# Bluetooth_Receiver.net
KiCad netlist of a schematic drawn in Altium Designer
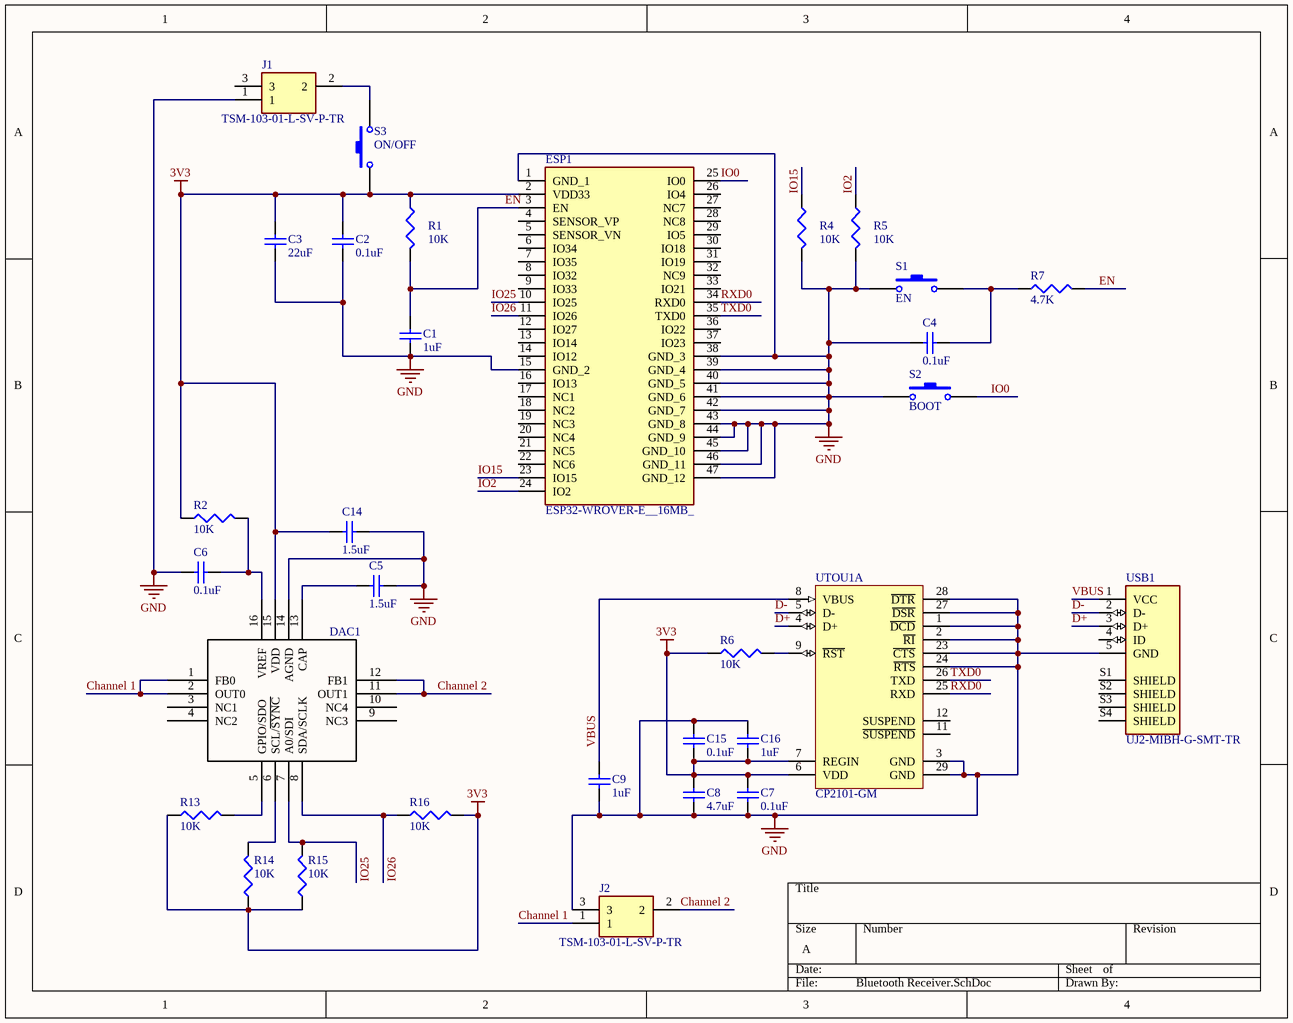
[diagram p0: Bluetooth Receiver.SchDoc]

(export (version "E")
  (design (tool "Eeschema 10.0.6"))
  (components
    (comp (ref "C1")
      (value "1uF")
      (footprint "1608[0603]")
      (description "Capacitor (Semiconductor SIM Model)")
      (fields (field (name "Comment") "Cap") (field (name "PUBLISHER") "Altium Limited"))
      (libsource (lib "Miscellaneous Devices") (part "Cap Semi"))
    )
    (comp (ref "C2")
      (value "0.1uF")
      (footprint "1608[0603]")
      (description "Capacitor (Semiconductor SIM Model)")
      (fields (field (name "Comment") "Cap") (field (name "PUBLISHER") "Altium Limited"))
      (libsource (lib "Miscellaneous Devices") (part "Cap Semi"))
    )
    (comp (ref "C3")
      (value "22uF")
      (footprint "1608[0603]")
      (description "Capacitor (Semiconductor SIM Model)")
      (fields (field (name "Comment") "Cap") (field (name "PUBLISHER") "Altium Limited"))
      (libsource (lib "Miscellaneous Devices") (part "Cap Semi"))
    )
    (comp (ref "C4")
      (value "0.1uF")
      (footprint "1608[0603]")
      (description "Capacitor (Semiconductor SIM Model)")
      (fields (field (name "Comment") "Cap") (field (name "PUBLISHER") "Altium Limited"))
      (libsource (lib "Miscellaneous Devices") (part "Cap Semi"))
    )
    (comp (ref "C5")
      (value "1.5uF")
      (footprint "1608[0603]")
      (description "Capacitor (Semiconductor SIM Model)")
      (fields (field (name "Comment") "Cap") (field (name "PUBLISHER") "Altium Limited"))
      (libsource (lib "Miscellaneous Devices") (part "Cap Semi"))
    )
    (comp (ref "C6")
      (value "0.1uF")
      (footprint "1608[0603]")
      (description "Capacitor (Semiconductor SIM Model)")
      (fields (field (name "Comment") "Cap") (field (name "PUBLISHER") "Altium Limited"))
      (libsource (lib "Miscellaneous Devices") (part "Cap Semi"))
    )
    (comp (ref "C7")
      (value "0.1uF")
      (footprint "1608[0603]")
      (description "Capacitor (Semiconductor SIM Model)")
      (fields (field (name "Comment") "Cap") (field (name "PUBLISHER") "Altium Limited"))
      (libsource (lib "Miscellaneous Devices") (part "Cap Semi"))
    )
    (comp (ref "C8")
      (value "4.7uF")
      (footprint "1608[0603]")
      (description "Capacitor (Semiconductor SIM Model)")
      (fields (field (name "Comment") "Cap") (field (name "PUBLISHER") "Altium Limited"))
      (libsource (lib "Miscellaneous Devices") (part "Cap Semi"))
    )
    (comp (ref "C9")
      (value "1uF")
      (footprint "1608[0603]")
      (description "Capacitor (Semiconductor SIM Model)")
      (fields (field (name "Comment") "Cap") (field (name "PUBLISHER") "Altium Limited"))
      (libsource (lib "Miscellaneous Devices") (part "Cap Semi"))
    )
    (comp (ref "C14")
      (value "1.5uF")
      (footprint "1608[0603]")
      (description "Capacitor (Semiconductor SIM Model)")
      (fields (field (name "Comment") "Cap") (field (name "PUBLISHER") "Altium Limited"))
      (libsource (lib "Miscellaneous Devices") (part "Cap Semi"))
    )
    (comp (ref "C15")
      (value "0.1uF")
      (footprint "1608[0603]")
      (description "Capacitor (Semiconductor SIM Model)")
      (fields (field (name "Comment") "Cap") (field (name "PUBLISHER") "Altium Limited"))
      (libsource (lib "Miscellaneous Devices") (part "Cap Semi"))
    )
    (comp (ref "C16")
      (value "1uF")
      (footprint "1608[0603]")
      (description "Capacitor (Semiconductor SIM Model)")
      (fields (field (name "Comment") "Cap") (field (name "PUBLISHER") "Altium Limited"))
      (libsource (lib "Miscellaneous Devices") (part "Cap Semi"))
    )
    (comp (ref "DAC1") (value "DAC6320") (footprint "DAC63202") (libsource (lib "DAC63202") (part "DAC6320")))
    (comp (ref "ESP1")
      (value "ESP32-WROVER-E__16MB_")
      (footprint "SamacSys:ESP32WROVERE16MB")
      (description "Integrated Circuit")
      (fields
        (field (name "MANUFACTURER_PART_NUMBER") "ESP32-WROVER-E (16MB)")
        (field (name "MOUSER PART NUMBER") "356-ESP32WRVE22864PC")
      )
      (libsource (lib "*") (part "ESP32-WROVER-E__16MB_"))
    )
    (comp (ref "J1")
      (value "TSM-103-01-L-SV-P-TR")
      (footprint "SamacSys:TSM10301LSVPTR")
      (description "Connector")
      (fields (field (name "MOUSER PART NUMBER") "200-TSM10301LSVPTR"))
      (libsource (lib "*") (part "TSM-103-01-L-SV-P-TR"))
    )
    (comp (ref "J2")
      (value "TSM-103-01-L-SV-P-TR")
      (footprint "SamacSys:TSM10301LSVPTR")
      (description "Connector")
      (fields (field (name "MOUSER PART NUMBER") "200-TSM10301LSVPTR"))
      (libsource (lib "*") (part "TSM-103-01-L-SV-P-TR"))
    )
    (comp (ref "R1")
      (value "10K")
      (footprint "J1-0603")
      (description "Resistor")
      (fields (field (name "Comment") "Res3") (field (name "PUBLISHER") "Altium Limited"))
      (libsource (lib "Miscellaneous Devices") (part "Res3"))
    )
    (comp (ref "R2")
      (value "10K")
      (footprint "J1-0603")
      (description "Resistor")
      (fields (field (name "Comment") "Res3") (field (name "PUBLISHER") "Altium Limited"))
      (libsource (lib "Miscellaneous Devices") (part "Res3"))
    )
    (comp (ref "R4")
      (value "10K")
      (footprint "J1-0603")
      (description "Resistor")
      (fields (field (name "Comment") "Res3") (field (name "PUBLISHER") "Altium Limited"))
      (libsource (lib "Miscellaneous Devices") (part "Res3"))
    )
    (comp (ref "R5")
      (value "10K")
      (footprint "J1-0603")
      (description "Resistor")
      (fields (field (name "Comment") "Res3") (field (name "PUBLISHER") "Altium Limited"))
      (libsource (lib "Miscellaneous Devices") (part "Res3"))
    )
    (comp (ref "R6")
      (value "10K")
      (footprint "J1-0603")
      (description "Resistor")
      (fields (field (name "Comment") "Res3") (field (name "PUBLISHER") "Altium Limited"))
      (libsource (lib "Miscellaneous Devices") (part "Res3"))
    )
    (comp (ref "R7")
      (value "4.7K")
      (footprint "J1-0603")
      (description "Resistor")
      (fields (field (name "Comment") "Res3") (field (name "PUBLISHER") "Altium Limited"))
      (libsource (lib "Miscellaneous Devices") (part "Res3"))
    )
    (comp (ref "R13")
      (value "10K")
      (footprint "J1-0603")
      (description "Resistor")
      (fields (field (name "Comment") "Res3") (field (name "PUBLISHER") "Altium Limited"))
      (libsource (lib "Miscellaneous Devices") (part "Res3"))
    )
    (comp (ref "R14")
      (value "10K")
      (footprint "J1-0603")
      (description "Resistor")
      (fields (field (name "Comment") "Res3") (field (name "PUBLISHER") "Altium Limited"))
      (libsource (lib "Miscellaneous Devices") (part "Res3"))
    )
    (comp (ref "R15")
      (value "10K")
      (footprint "J1-0603")
      (description "Resistor")
      (fields (field (name "Comment") "Res3") (field (name "PUBLISHER") "Altium Limited"))
      (libsource (lib "Miscellaneous Devices") (part "Res3"))
    )
    (comp (ref "R16")
      (value "10K")
      (footprint "J1-0603")
      (description "Resistor")
      (fields (field (name "Comment") "Res3") (field (name "PUBLISHER") "Altium Limited"))
      (libsource (lib "Miscellaneous Devices") (part "Res3"))
    )
    (comp (ref "S1")
      (value "EN")
      (footprint "R1966ABLKBLKEF:R1966ABLKBLKEF")
      (description "Switch")
      (fields (field (name "PUBLISHER") "Altium Limited"))
      (libsource (lib "Miscellaneous Devices") (part "SW-PB"))
    )
    (comp (ref "S2")
      (value "BOOT")
      (footprint "R1966ABLKBLKEF:R1966ABLKBLKEF")
      (description "Switch")
      (fields (field (name "PUBLISHER") "Altium Limited"))
      (libsource (lib "Miscellaneous Devices") (part "SW-PB"))
    )
    (comp (ref "S3")
      (value "ON/OFF")
      (footprint "R1966ABLKBLKEF:R1966ABLKBLKEF")
      (description "Switch")
      (fields (field (name "PUBLISHER") "Altium Limited"))
      (libsource (lib "Miscellaneous Devices") (part "SW-PB"))
    )
    (comp (ref "USB1")
      (value "UJ2-MIBH-G-SMT-TR")
      (footprint "CUI_UJ2-MIBH-G-SMT-TR:CUI_UJ2-MIBH-G-SMT-TR")
      (description "USB micro B type receptacle")
      (libsource (lib "UJ2-MIBH-G-SMT-TR") (part "UJ2-MIBH-G-SMT-TR"))
    )
    (comp (ref "UTOU1")
      (value "CP2101-GM")
      (footprint "Silicon_Labs_CP2101_GM_0:SLAB-QFN-28-3125x3125TP_A_N")
      (description "Single-Chip USB to UART Bridge, 512 Bytes EEPROM, -40 to 85 degC, 28-pin QFN, Tube")
      (fields (field (name "MANUFACTURER") "Silicon Labs"))
      (libsource (lib "Silicon_Labs_CP2101_GM") (part "CP2101-GM"))
    )
  )
  (nets
    (net (code "1") (name "/Channel 1") (class "Default")
      (node (ref "DAC1") (pin "1") (pinfunction "FB0_1") (pintype "passive"))
      (node (ref "DAC1") (pin "2") (pinfunction "OUT0_2") (pintype "passive"))
      (node (ref "J2") (pin "1") (pinfunction "1_1") (pintype "passive"))
    )
    (net (code "2") (name "/Channel 2") (class "Default")
      (node (ref "DAC1") (pin "11") (pinfunction "OUT1_11") (pintype "passive"))
      (node (ref "DAC1") (pin "12") (pinfunction "FB1_12") (pintype "passive"))
      (node (ref "J2") (pin "2") (pinfunction "2_2") (pintype "passive"))
    )
    (net (code "3") (name "/D+") (class "Default")
      (node (ref "USB1") (pin "3") (pinfunction "D+_3") (pintype "bidirectional"))
      (node (ref "UTOU1") (pin "4") (pinfunction "D+_4") (pintype "bidirectional"))
    )
    (net (code "4") (name "/D-") (class "Default")
      (node (ref "USB1") (pin "2") (pinfunction "D-_2") (pintype "bidirectional"))
      (node (ref "UTOU1") (pin "5") (pinfunction "D-_5") (pintype "bidirectional"))
    )
    (net (code "5") (name "/EN") (class "Default")
      (node (ref "C1") (pin "2") (pinfunction "2_2") (pintype "passive"))
      (node (ref "ESP1") (pin "3") (pinfunction "EN_3") (pintype "passive"))
      (node (ref "R1") (pin "2") (pinfunction "2_2") (pintype "passive"))
      (node (ref "R7") (pin "2") (pinfunction "2_2") (pintype "passive"))
    )
    (net (code "6") (name "/IO0") (class "Default")
      (node (ref "ESP1") (pin "25") (pinfunction "IO0_25") (pintype "passive"))
      (node (ref "S2") (pin "2") (pinfunction "2_2") (pintype "passive"))
    )
    (net (code "7") (name "/IO2") (class "Default")
      (node (ref "ESP1") (pin "24") (pinfunction "IO2_24") (pintype "passive"))
      (node (ref "R5") (pin "1") (pinfunction "1_1") (pintype "passive"))
    )
    (net (code "8") (name "/IO15") (class "Default")
      (node (ref "ESP1") (pin "23") (pinfunction "IO15_23") (pintype "passive"))
      (node (ref "R4") (pin "1") (pinfunction "1_1") (pintype "passive"))
    )
    (net (code "9") (name "/IO25") (class "Default")
      (node (ref "DAC1") (pin "7") (pinfunction "A0/SDI_7") (pintype "passive"))
      (node (ref "ESP1") (pin "10") (pinfunction "IO25_10") (pintype "passive"))
      (node (ref "R15") (pin "2") (pinfunction "2_2") (pintype "passive"))
    )
    (net (code "10") (name "/IO26") (class "Default")
      (node (ref "DAC1") (pin "8") (pinfunction "SDA/SCLK_8") (pintype "passive"))
      (node (ref "ESP1") (pin "11") (pinfunction "IO26_11") (pintype "passive"))
      (node (ref "R16") (pin "1") (pinfunction "1_1") (pintype "passive"))
    )
    (net (code "11") (name "/RXD0") (class "Default")
      (node (ref "ESP1") (pin "34") (pinfunction "RXD0_34") (pintype "passive"))
      (node (ref "UTOU1") (pin "25") (pinfunction "RXD_25") (pintype "passive"))
    )
    (net (code "12") (name "/TXD0") (class "Default")
      (node (ref "ESP1") (pin "35") (pinfunction "TXD0_35") (pintype "passive"))
      (node (ref "UTOU1") (pin "26") (pinfunction "TXD_26") (pintype "passive"))
    )
    (net (code "13") (name "/VBUS") (class "Default")
      (node (ref "C9") (pin "2") (pinfunction "2_2") (pintype "passive"))
      (node (ref "USB1") (pin "1") (pinfunction "VCC_1") (pintype "power_in"))
      (node (ref "UTOU1") (pin "8") (pinfunction "VBUS_8") (pintype "input"))
    )
    (net (code "14") (name "3V3") (class "Default")
      (node (ref "C14") (pin "2") (pinfunction "2_2") (pintype "passive"))
      (node (ref "C15") (pin "1") (pinfunction "1_1") (pintype "passive"))
      (node (ref "C16") (pin "1") (pinfunction "1_1") (pintype "passive"))
      (node (ref "C2") (pin "2") (pinfunction "2_2") (pintype "passive"))
      (node (ref "C3") (pin "2") (pinfunction "2_2") (pintype "passive"))
      (node (ref "C7") (pin "2") (pinfunction "2_2") (pintype "passive"))
      (node (ref "C8") (pin "2") (pinfunction "2_2") (pintype "passive"))
      (node (ref "DAC1") (pin "15") (pinfunction "VDD_15") (pintype "passive"))
      (node (ref "ESP1") (pin "2") (pinfunction "VDD33_2") (pintype "passive"))
      (node (ref "R1") (pin "1") (pinfunction "1_1") (pintype "passive"))
      (node (ref "R13") (pin "1") (pinfunction "1_1") (pintype "passive"))
      (node (ref "R14") (pin "1") (pinfunction "1_1") (pintype "passive"))
      (node (ref "R15") (pin "1") (pinfunction "1_1") (pintype "passive"))
      (node (ref "R16") (pin "2") (pinfunction "2_2") (pintype "passive"))
      (node (ref "R2") (pin "1") (pinfunction "1_1") (pintype "passive"))
      (node (ref "R6") (pin "1") (pinfunction "1_1") (pintype "passive"))
      (node (ref "S3") (pin "1") (pinfunction "1_1") (pintype "passive"))
      (node (ref "UTOU1") (pin "6") (pinfunction "VDD_6") (pintype "power_in"))
      (node (ref "UTOU1") (pin "7") (pinfunction "REGIN_7") (pintype "power_in"))
    )
    (net (code "15") (name "GND") (class "Default")
      (node (ref "C1") (pin "1") (pinfunction "1_1") (pintype "passive"))
      (node (ref "C14") (pin "1") (pinfunction "1_1") (pintype "passive"))
      (node (ref "C15") (pin "2") (pinfunction "2_2") (pintype "passive"))
      (node (ref "C16") (pin "2") (pinfunction "2_2") (pintype "passive"))
      (node (ref "C2") (pin "1") (pinfunction "1_1") (pintype "passive"))
      (node (ref "C3") (pin "1") (pinfunction "1_1") (pintype "passive"))
      (node (ref "C4") (pin "2") (pinfunction "2_2") (pintype "passive"))
      (node (ref "C5") (pin "1") (pinfunction "1_1") (pintype "passive"))
      (node (ref "C6") (pin "2") (pinfunction "2_2") (pintype "passive"))
      (node (ref "C7") (pin "1") (pinfunction "1_1") (pintype "passive"))
      (node (ref "C8") (pin "1") (pinfunction "1_1") (pintype "passive"))
      (node (ref "C9") (pin "1") (pinfunction "1_1") (pintype "passive"))
      (node (ref "DAC1") (pin "14") (pinfunction "AGND_14") (pintype "passive"))
      (node (ref "ESP1") (pin "1") (pinfunction "GND_1_1") (pintype "passive"))
      (node (ref "ESP1") (pin "15") (pinfunction "GND_2_15") (pintype "passive"))
      (node (ref "ESP1") (pin "38") (pinfunction "GND_3_38") (pintype "passive"))
      (node (ref "ESP1") (pin "39") (pinfunction "GND_4_39") (pintype "passive"))
      (node (ref "ESP1") (pin "40") (pinfunction "GND_5_40") (pintype "passive"))
      (node (ref "ESP1") (pin "41") (pinfunction "GND_6_41") (pintype "passive"))
      (node (ref "ESP1") (pin "42") (pinfunction "GND_7_42") (pintype "passive"))
      (node (ref "ESP1") (pin "43") (pinfunction "GND_8_43") (pintype "passive"))
      (node (ref "ESP1") (pin "44") (pinfunction "GND_9_44") (pintype "passive"))
      (node (ref "ESP1") (pin "45") (pinfunction "GND_10_45") (pintype "passive"))
      (node (ref "ESP1") (pin "46") (pinfunction "GND_11_46") (pintype "passive"))
      (node (ref "ESP1") (pin "47") (pinfunction "GND_12_47") (pintype "passive"))
      (node (ref "J1") (pin "1") (pinfunction "1_1") (pintype "passive"))
      (node (ref "J2") (pin "3") (pinfunction "3_3") (pintype "passive"))
      (node (ref "R4") (pin "2") (pinfunction "2_2") (pintype "passive"))
      (node (ref "R5") (pin "2") (pinfunction "2_2") (pintype "passive"))
      (node (ref "S1") (pin "1") (pinfunction "1_1") (pintype "passive"))
      (node (ref "S2") (pin "1") (pinfunction "1_1") (pintype "passive"))
      (node (ref "USB1") (pin "5") (pinfunction "GND_5") (pintype "power_in"))
      (node (ref "UTOU1") (pin "1") (pinfunction "~{DCD}_1") (pintype "passive"))
      (node (ref "UTOU1") (pin "2") (pinfunction "~{RI}_2") (pintype "passive"))
      (node (ref "UTOU1") (pin "23") (pinfunction "~{CTS}_23") (pintype "passive"))
      (node (ref "UTOU1") (pin "24") (pinfunction "~{RTS}_24") (pintype "passive"))
      (node (ref "UTOU1") (pin "27") (pinfunction "~{DSR}_27") (pintype "passive"))
      (node (ref "UTOU1") (pin "28") (pinfunction "~{DTR}_28") (pintype "passive"))
      (node (ref "UTOU1") (pin "29") (pinfunction "GND_29") (pintype "power_in"))
      (node (ref "UTOU1") (pin "3") (pinfunction "GND_3") (pintype "power_in"))
    )
    (net (code "16") (name "Net-(C4-Pad1)") (class "Default")
      (node (ref "C4") (pin "1") (pinfunction "1_1") (pintype "passive"))
      (node (ref "R7") (pin "1") (pinfunction "1_1") (pintype "passive"))
      (node (ref "S1") (pin "2") (pinfunction "2_2") (pintype "passive"))
    )
    (net (code "17") (name "Net-(DAC1-CAP)") (class "Default")
      (node (ref "C5") (pin "2") (pinfunction "2_2") (pintype "passive"))
      (node (ref "DAC1") (pin "13") (pinfunction "CAP_13") (pintype "passive"))
    )
    (net (code "18") (name "Net-(DAC1-GPIO{slash}SDO)") (class "Default")
      (node (ref "DAC1") (pin "5") (pinfunction "GPIO/SDO_5") (pintype "passive"))
      (node (ref "R13") (pin "2") (pinfunction "2_2") (pintype "passive"))
    )
    (net (code "19") (name "Net-(DAC1-SCL{slash}~{SYNC})") (class "Default")
      (node (ref "DAC1") (pin "6") (pinfunction "SCL/~{SYNC}_6") (pintype "passive"))
      (node (ref "R14") (pin "2") (pinfunction "2_2") (pintype "passive"))
    )
    (net (code "20") (name "Net-(DAC1-VREF)") (class "Default")
      (node (ref "C6") (pin "1") (pinfunction "1_1") (pintype "passive"))
      (node (ref "DAC1") (pin "16") (pinfunction "VREF_16") (pintype "passive"))
      (node (ref "R2") (pin "2") (pinfunction "2_2") (pintype "passive"))
    )
    (net (code "21") (name "Net-(J1-Pad2)") (class "Default")
      (node (ref "J1") (pin "2") (pinfunction "2_2") (pintype "passive"))
      (node (ref "S3") (pin "2") (pinfunction "2_2") (pintype "passive"))
    )
    (net (code "22") (name "Net-(UTOU1A-~{RST})") (class "Default")
      (node (ref "R6") (pin "2") (pinfunction "2_2") (pintype "passive"))
      (node (ref "UTOU1") (pin "9") (pinfunction "~{RST}_9") (pintype "bidirectional"))
    )
    (net (code "23") (name "unconnected-(DAC1-NC1-Pad3)") (class "Default")
      (node (ref "DAC1") (pin "3") (pinfunction "NC1_3") (pintype "passive"))
    )
    (net (code "24") (name "unconnected-(DAC1-NC2-Pad4)") (class "Default")
      (node (ref "DAC1") (pin "4") (pinfunction "NC2_4") (pintype "passive"))
    )
    (net (code "25") (name "unconnected-(DAC1-NC3-Pad9)") (class "Default")
      (node (ref "DAC1") (pin "9") (pinfunction "NC3_9") (pintype "passive"))
    )
    (net (code "26") (name "unconnected-(DAC1-NC4-Pad10)") (class "Default")
      (node (ref "DAC1") (pin "10") (pinfunction "NC4_10") (pintype "passive"))
    )
    (net (code "27") (name "unconnected-(ESP1-IO4-Pad26)") (class "Default")
      (node (ref "ESP1") (pin "26") (pinfunction "IO4_26") (pintype "passive"))
    )
    (net (code "28") (name "unconnected-(ESP1-IO5-Pad29)") (class "Default")
      (node (ref "ESP1") (pin "29") (pinfunction "IO5_29") (pintype "passive"))
    )
    (net (code "29") (name "unconnected-(ESP1-IO12-Pad14)") (class "Default")
      (node (ref "ESP1") (pin "14") (pinfunction "IO12_14") (pintype "passive"))
    )
    (net (code "30") (name "unconnected-(ESP1-IO13-Pad16)") (class "Default")
      (node (ref "ESP1") (pin "16") (pinfunction "IO13_16") (pintype "passive"))
    )
    (net (code "31") (name "unconnected-(ESP1-IO14-Pad13)") (class "Default")
      (node (ref "ESP1") (pin "13") (pinfunction "IO14_13") (pintype "passive"))
    )
    (net (code "32") (name "unconnected-(ESP1-IO18-Pad30)") (class "Default")
      (node (ref "ESP1") (pin "30") (pinfunction "IO18_30") (pintype "passive"))
    )
    (net (code "33") (name "unconnected-(ESP1-IO19-Pad31)") (class "Default")
      (node (ref "ESP1") (pin "31") (pinfunction "IO19_31") (pintype "passive"))
    )
    (net (code "34") (name "unconnected-(ESP1-IO21-Pad33)") (class "Default")
      (node (ref "ESP1") (pin "33") (pinfunction "IO21_33") (pintype "passive"))
    )
    (net (code "35") (name "unconnected-(ESP1-IO22-Pad36)") (class "Default")
      (node (ref "ESP1") (pin "36") (pinfunction "IO22_36") (pintype "passive"))
    )
    (net (code "36") (name "unconnected-(ESP1-IO23-Pad37)") (class "Default")
      (node (ref "ESP1") (pin "37") (pinfunction "IO23_37") (pintype "passive"))
    )
    (net (code "37") (name "unconnected-(ESP1-IO27-Pad12)") (class "Default")
      (node (ref "ESP1") (pin "12") (pinfunction "IO27_12") (pintype "passive"))
    )
    (net (code "38") (name "unconnected-(ESP1-IO32-Pad8)") (class "Default")
      (node (ref "ESP1") (pin "8") (pinfunction "IO32_8") (pintype "passive"))
    )
    (net (code "39") (name "unconnected-(ESP1-IO33-Pad9)") (class "Default")
      (node (ref "ESP1") (pin "9") (pinfunction "IO33_9") (pintype "passive"))
    )
    (net (code "40") (name "unconnected-(ESP1-IO34-Pad6)") (class "Default")
      (node (ref "ESP1") (pin "6") (pinfunction "IO34_6") (pintype "passive"))
    )
    (net (code "41") (name "unconnected-(ESP1-IO35-Pad7)") (class "Default")
      (node (ref "ESP1") (pin "7") (pinfunction "IO35_7") (pintype "passive"))
    )
    (net (code "42") (name "unconnected-(ESP1-NC1-Pad17)") (class "Default")
      (node (ref "ESP1") (pin "17") (pinfunction "NC1_17") (pintype "passive"))
    )
    (net (code "43") (name "unconnected-(ESP1-NC2-Pad18)") (class "Default")
      (node (ref "ESP1") (pin "18") (pinfunction "NC2_18") (pintype "passive"))
    )
    (net (code "44") (name "unconnected-(ESP1-NC3-Pad19)") (class "Default")
      (node (ref "ESP1") (pin "19") (pinfunction "NC3_19") (pintype "passive"))
    )
    (net (code "45") (name "unconnected-(ESP1-NC4-Pad20)") (class "Default")
      (node (ref "ESP1") (pin "20") (pinfunction "NC4_20") (pintype "passive"))
    )
    (net (code "46") (name "unconnected-(ESP1-NC5-Pad21)") (class "Default")
      (node (ref "ESP1") (pin "21") (pinfunction "NC5_21") (pintype "passive"))
    )
    (net (code "47") (name "unconnected-(ESP1-NC6-Pad22)") (class "Default")
      (node (ref "ESP1") (pin "22") (pinfunction "NC6_22") (pintype "passive"))
    )
    (net (code "48") (name "unconnected-(ESP1-NC7-Pad27)") (class "Default")
      (node (ref "ESP1") (pin "27") (pinfunction "NC7_27") (pintype "passive"))
    )
    (net (code "49") (name "unconnected-(ESP1-NC8-Pad28)") (class "Default")
      (node (ref "ESP1") (pin "28") (pinfunction "NC8_28") (pintype "passive"))
    )
    (net (code "50") (name "unconnected-(ESP1-NC9-Pad32)") (class "Default")
      (node (ref "ESP1") (pin "32") (pinfunction "NC9_32") (pintype "passive"))
    )
    (net (code "51") (name "unconnected-(ESP1-SENSOR_VN-Pad5)") (class "Default")
      (node (ref "ESP1") (pin "5") (pinfunction "SENSOR_VN_5") (pintype "passive"))
    )
    (net (code "52") (name "unconnected-(ESP1-SENSOR_VP-Pad4)") (class "Default")
      (node (ref "ESP1") (pin "4") (pinfunction "SENSOR_VP_4") (pintype "passive"))
    )
    (net (code "53") (name "unconnected-(J1-Pad3)") (class "Default")
      (node (ref "J1") (pin "3") (pinfunction "3_3") (pintype "passive"))
    )
    (net (code "54") (name "unconnected-(USB1-ID-Pad4)") (class "Default")
      (node (ref "USB1") (pin "4") (pinfunction "ID_4") (pintype "bidirectional"))
    )
    (net (code "55") (name "unconnected-(USB1-SHIELD-PadS1)") (class "Default")
      (node (ref "USB1") (pin "S1") (pinfunction "SHIELD_S1") (pintype "passive"))
    )
    (net (code "56") (name "unconnected-(USB1-SHIELD-PadS2)") (class "Default")
      (node (ref "USB1") (pin "S2") (pinfunction "SHIELD_S2") (pintype "passive"))
    )
    (net (code "57") (name "unconnected-(USB1-SHIELD-PadS3)") (class "Default")
      (node (ref "USB1") (pin "S3") (pinfunction "SHIELD_S3") (pintype "passive"))
    )
    (net (code "58") (name "unconnected-(USB1-SHIELD-PadS4)") (class "Default")
      (node (ref "USB1") (pin "S4") (pinfunction "SHIELD_S4") (pintype "passive"))
    )
    (net (code "59") (name "unconnected-(UTOU1A-SUSPEND-Pad12)") (class "Default")
      (node (ref "UTOU1") (pin "12") (pinfunction "SUSPEND_12") (pintype "passive"))
    )
    (net (code "60") (name "unconnected-(UTOU1A-~{SUSPEND}-Pad11)") (class "Default")
      (node (ref "UTOU1") (pin "11") (pinfunction "~{SUSPEND}_11") (pintype "passive"))
    )
  )
)
